# aria-BOB.net
KiCad netlist of a schematic drawn in EAGLE
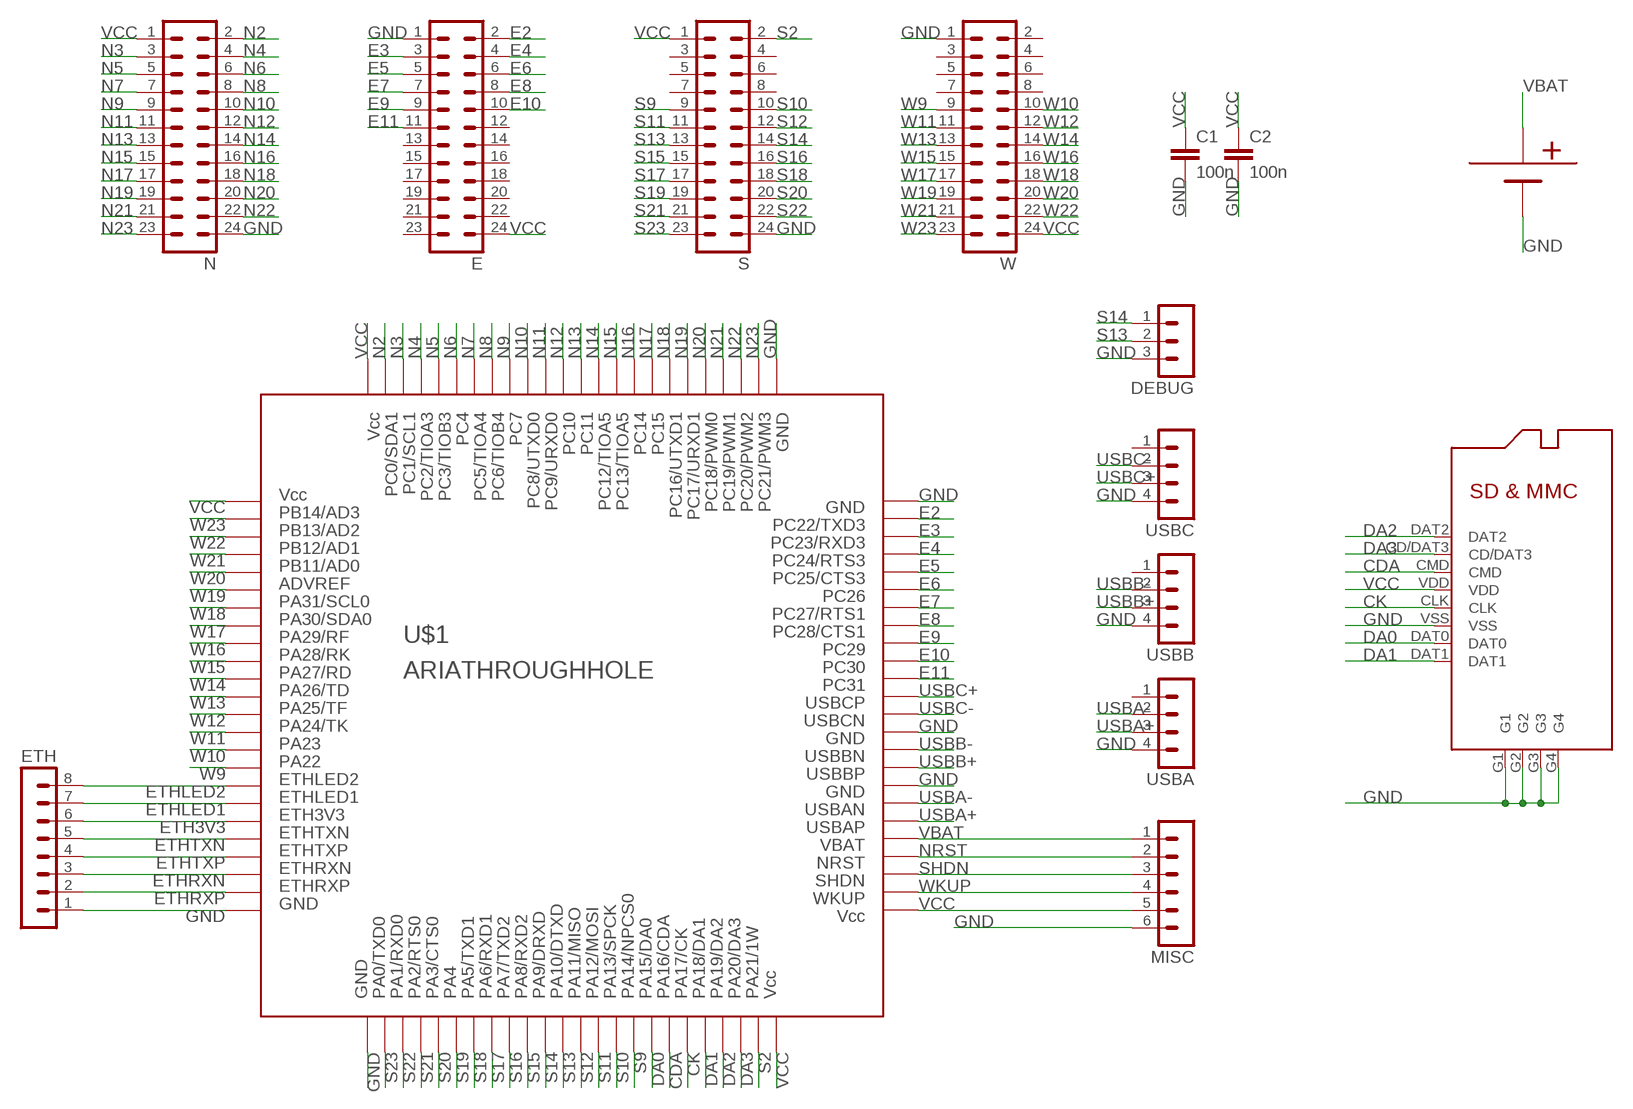
[diagram p0: schematic, sheet 1]

(export (version "E")
  (design (tool "Eeschema 10.0.6"))
  (components
    (comp (ref "C1")
      (value "100n")
      (footprint "eagle-import:C0603")
      (libsource (lib "eagle-import") (part "C-EUC0603"))
    )
    (comp (ref "C2")
      (value "100n")
      (footprint "eagle-import:C0603")
      (libsource (lib "eagle-import") (part "C-EUC0603"))
    )
    (comp (ref "DEBUG")
      (value "MA03-1")
      (footprint "eagle-import:MA03-1")
      (libsource (lib "eagle-import") (part "MA03-1"))
    )
    (comp (ref "E")
      (value "MA12-2")
      (footprint "eagle-import:MA12-2")
      (libsource (lib "eagle-import") (part "MA12-2"))
    )
    (comp (ref "ETH")
      (value "MA08-1")
      (footprint "eagle-import:MA08-1")
      (libsource (lib "eagle-import") (part "MA08-1"))
    )
    (comp (ref "MISC")
      (value "MA06-1")
      (footprint "eagle-import:MA06-1")
      (libsource (lib "eagle-import") (part "MA06-1"))
    )
    (comp (ref "N")
      (value "MA12-2")
      (footprint "eagle-import:MA12-2")
      (libsource (lib "eagle-import") (part "MA12-2"))
    )
    (comp (ref "S")
      (value "MA12-2")
      (footprint "eagle-import:MA12-2")
      (libsource (lib "eagle-import") (part "MA12-2"))
    )
    (comp (ref "U$1")
      (value "ARIATHROUGHHOLE")
      (footprint "eagle-import:ARIA-TROUGHHOLE")
      (libsource (lib "eagle-import") (part "ARIATHROUGHHOLE"))
    )
    (comp (ref "U$3")
      (value "BAT")
      (footprint "eagle-import:BAT-CR1220")
      (libsource (lib "eagle-import") (part "BAT"))
    )
    (comp (ref "U$4")
      (value "MICRO-SD")
      (footprint "eagle-import:MISCRO-SD")
      (libsource (lib "eagle-import") (part "MICRO-SD"))
    )
    (comp (ref "USBA")
      (value "MA04-1")
      (footprint "eagle-import:MA04-1")
      (libsource (lib "eagle-import") (part "MA04-1"))
    )
    (comp (ref "USBB")
      (value "MA04-1")
      (footprint "eagle-import:MA04-1")
      (libsource (lib "eagle-import") (part "MA04-1"))
    )
    (comp (ref "USBC")
      (value "MA04-1")
      (footprint "eagle-import:MA04-1")
      (libsource (lib "eagle-import") (part "MA04-1"))
    )
    (comp (ref "W")
      (value "MA12-2")
      (footprint "eagle-import:MA12-2")
      (libsource (lib "eagle-import") (part "MA12-2"))
    )
  )
  (nets
    (net (code "1") (name "/CDA") (class "Default")
      (node (ref "U$1") (pin "S7") (pinfunction "S7_S7") (pintype "bidirectional"))
      (node (ref "U$4") (pin "CMD") (pinfunction "CMD_CMD") (pintype "input"))
    )
    (net (code "2") (name "/CK") (class "Default")
      (node (ref "U$1") (pin "S6") (pinfunction "S6_S6") (pintype "bidirectional"))
      (node (ref "U$4") (pin "CLK") (pinfunction "CLK_CLK") (pintype "input"))
    )
    (net (code "3") (name "/DA0") (class "Default")
      (node (ref "U$1") (pin "S8") (pinfunction "S8_S8") (pintype "bidirectional"))
      (node (ref "U$4") (pin "DAT0") (pinfunction "DAT0_DAT0") (pintype "input"))
    )
    (net (code "4") (name "/DA1") (class "Default")
      (node (ref "U$1") (pin "S5") (pinfunction "S5_S5") (pintype "bidirectional"))
      (node (ref "U$4") (pin "DAT1") (pinfunction "DAT1_DAT1") (pintype "output"))
    )
    (net (code "5") (name "/DA2") (class "Default")
      (node (ref "U$1") (pin "S4") (pinfunction "S4_S4") (pintype "bidirectional"))
      (node (ref "U$4") (pin "DAT2") (pinfunction "DAT2_DAT2") (pintype "bidirectional"))
    )
    (net (code "6") (name "/DA3") (class "Default")
      (node (ref "U$1") (pin "S3") (pinfunction "S3_S3") (pintype "bidirectional"))
      (node (ref "U$4") (pin "CD/DAT3") (pinfunction "CD/DAT3_CD/DAT3") (pintype "bidirectional"))
    )
    (net (code "7") (name "/E2") (class "Default")
      (node (ref "E") (pin "2") (pinfunction "2_2") (pintype "passive"))
      (node (ref "U$1") (pin "E2") (pinfunction "E2_E2") (pintype "bidirectional"))
    )
    (net (code "8") (name "/E3") (class "Default")
      (node (ref "E") (pin "3") (pinfunction "3_3") (pintype "passive"))
      (node (ref "U$1") (pin "E3") (pinfunction "E3_E3") (pintype "bidirectional"))
    )
    (net (code "9") (name "/E4") (class "Default")
      (node (ref "E") (pin "4") (pinfunction "4_4") (pintype "passive"))
      (node (ref "U$1") (pin "E4") (pinfunction "E4_E4") (pintype "bidirectional"))
    )
    (net (code "10") (name "/E5") (class "Default")
      (node (ref "E") (pin "5") (pinfunction "5_5") (pintype "passive"))
      (node (ref "U$1") (pin "E5") (pinfunction "E5_E5") (pintype "bidirectional"))
    )
    (net (code "11") (name "/E6") (class "Default")
      (node (ref "E") (pin "6") (pinfunction "6_6") (pintype "passive"))
      (node (ref "U$1") (pin "E6") (pinfunction "E6_E6") (pintype "bidirectional"))
    )
    (net (code "12") (name "/E7") (class "Default")
      (node (ref "E") (pin "7") (pinfunction "7_7") (pintype "passive"))
      (node (ref "U$1") (pin "E7") (pinfunction "E7_E7") (pintype "bidirectional"))
    )
    (net (code "13") (name "/E8") (class "Default")
      (node (ref "E") (pin "8") (pinfunction "8_8") (pintype "passive"))
      (node (ref "U$1") (pin "E8") (pinfunction "E8_E8") (pintype "bidirectional"))
    )
    (net (code "14") (name "/E9") (class "Default")
      (node (ref "E") (pin "9") (pinfunction "9_9") (pintype "passive"))
      (node (ref "U$1") (pin "E9") (pinfunction "E9_E9") (pintype "bidirectional"))
    )
    (net (code "15") (name "/E10") (class "Default")
      (node (ref "E") (pin "10") (pinfunction "10_10") (pintype "passive"))
      (node (ref "U$1") (pin "E10") (pinfunction "E10_E10") (pintype "bidirectional"))
    )
    (net (code "16") (name "/E11") (class "Default")
      (node (ref "E") (pin "11") (pinfunction "11_11") (pintype "passive"))
      (node (ref "U$1") (pin "E11") (pinfunction "E11_E11") (pintype "bidirectional"))
    )
    (net (code "17") (name "/ETH3V3") (class "Default")
      (node (ref "ETH") (pin "6") (pinfunction "6_6") (pintype "passive"))
      (node (ref "U$1") (pin "W6") (pinfunction "W6_W6") (pintype "bidirectional"))
    )
    (net (code "18") (name "/ETHLED1") (class "Default")
      (node (ref "ETH") (pin "7") (pinfunction "7_7") (pintype "passive"))
      (node (ref "U$1") (pin "W7") (pinfunction "W7_W7") (pintype "bidirectional"))
    )
    (net (code "19") (name "/ETHLED2") (class "Default")
      (node (ref "ETH") (pin "8") (pinfunction "8_8") (pintype "passive"))
      (node (ref "U$1") (pin "W8") (pinfunction "W8_W8") (pintype "bidirectional"))
    )
    (net (code "20") (name "/ETHRXN") (class "Default")
      (node (ref "ETH") (pin "3") (pinfunction "3_3") (pintype "passive"))
      (node (ref "U$1") (pin "W3") (pinfunction "W3_W3") (pintype "bidirectional"))
    )
    (net (code "21") (name "/ETHRXP") (class "Default")
      (node (ref "ETH") (pin "2") (pinfunction "2_2") (pintype "passive"))
      (node (ref "U$1") (pin "W2") (pinfunction "W2_W2") (pintype "bidirectional"))
    )
    (net (code "22") (name "/ETHTXN") (class "Default")
      (node (ref "ETH") (pin "5") (pinfunction "5_5") (pintype "passive"))
      (node (ref "U$1") (pin "W5") (pinfunction "W5_W5") (pintype "bidirectional"))
    )
    (net (code "23") (name "/ETHTXP") (class "Default")
      (node (ref "ETH") (pin "4") (pinfunction "4_4") (pintype "passive"))
      (node (ref "U$1") (pin "W4") (pinfunction "W4_W4") (pintype "bidirectional"))
    )
    (net (code "24") (name "/GND") (class "Default")
      (node (ref "C1") (pin "2") (pinfunction "2_2") (pintype "passive"))
      (node (ref "C2") (pin "2") (pinfunction "2_2") (pintype "passive"))
      (node (ref "DEBUG") (pin "3") (pinfunction "3_3") (pintype "passive"))
      (node (ref "E") (pin "1") (pinfunction "1_1") (pintype "passive"))
      (node (ref "ETH") (pin "1") (pinfunction "1_1") (pintype "passive"))
      (node (ref "MISC") (pin "6") (pinfunction "6_6") (pintype "passive"))
      (node (ref "N") (pin "24") (pinfunction "24_24") (pintype "passive"))
      (node (ref "S") (pin "24") (pinfunction "24_24") (pintype "passive"))
      (node (ref "U$1") (pin "E1") (pinfunction "E1_E1") (pintype "bidirectional"))
      (node (ref "U$1") (pin "E14") (pinfunction "E14_E14") (pintype "bidirectional"))
      (node (ref "U$1") (pin "E17") (pinfunction "E17_E17") (pintype "bidirectional"))
      (node (ref "U$1") (pin "N24") (pinfunction "N24_N24") (pintype "bidirectional"))
      (node (ref "U$1") (pin "S24") (pinfunction "S24_S24") (pintype "bidirectional"))
      (node (ref "U$1") (pin "W1") (pinfunction "W1_W1") (pintype "bidirectional"))
      (node (ref "U$3") (pin "BAT-") (pinfunction "BAT-_BAT-") (pintype "bidirectional"))
      (node (ref "U$4") (pin "G1") (pinfunction "G1_G1") (pintype "bidirectional"))
      (node (ref "U$4") (pin "G2") (pinfunction "G2_G2") (pintype "bidirectional"))
      (node (ref "U$4") (pin "G3") (pinfunction "G3_G3") (pintype "bidirectional"))
      (node (ref "U$4") (pin "G4") (pinfunction "G4_G4") (pintype "bidirectional"))
      (node (ref "U$4") (pin "VSS") (pinfunction "VSS_VSS") (pintype "power_in"))
      (node (ref "USBA") (pin "4") (pinfunction "4_4") (pintype "passive"))
      (node (ref "USBB") (pin "4") (pinfunction "4_4") (pintype "passive"))
      (node (ref "USBC") (pin "4") (pinfunction "4_4") (pintype "passive"))
      (node (ref "W") (pin "1") (pinfunction "1_1") (pintype "passive"))
    )
    (net (code "25") (name "/N2") (class "Default")
      (node (ref "N") (pin "2") (pinfunction "2_2") (pintype "passive"))
      (node (ref "U$1") (pin "N2") (pinfunction "N2_N2") (pintype "bidirectional"))
    )
    (net (code "26") (name "/N3") (class "Default")
      (node (ref "N") (pin "3") (pinfunction "3_3") (pintype "passive"))
      (node (ref "U$1") (pin "N3") (pinfunction "N3_N3") (pintype "bidirectional"))
    )
    (net (code "27") (name "/N4") (class "Default")
      (node (ref "N") (pin "4") (pinfunction "4_4") (pintype "passive"))
      (node (ref "U$1") (pin "N4") (pinfunction "N4_N4") (pintype "bidirectional"))
    )
    (net (code "28") (name "/N5") (class "Default")
      (node (ref "N") (pin "5") (pinfunction "5_5") (pintype "passive"))
      (node (ref "U$1") (pin "N5") (pinfunction "N5_N5") (pintype "bidirectional"))
    )
    (net (code "29") (name "/N6") (class "Default")
      (node (ref "N") (pin "6") (pinfunction "6_6") (pintype "passive"))
      (node (ref "U$1") (pin "N6") (pinfunction "N6_N6") (pintype "bidirectional"))
    )
    (net (code "30") (name "/N7") (class "Default")
      (node (ref "N") (pin "7") (pinfunction "7_7") (pintype "passive"))
      (node (ref "U$1") (pin "N7") (pinfunction "N7_N7") (pintype "bidirectional"))
    )
    (net (code "31") (name "/N8") (class "Default")
      (node (ref "N") (pin "8") (pinfunction "8_8") (pintype "passive"))
      (node (ref "U$1") (pin "N8") (pinfunction "N8_N8") (pintype "bidirectional"))
    )
    (net (code "32") (name "/N9") (class "Default")
      (node (ref "N") (pin "9") (pinfunction "9_9") (pintype "passive"))
      (node (ref "U$1") (pin "N9") (pinfunction "N9_N9") (pintype "bidirectional"))
    )
    (net (code "33") (name "/N10") (class "Default")
      (node (ref "N") (pin "10") (pinfunction "10_10") (pintype "passive"))
      (node (ref "U$1") (pin "N10") (pinfunction "N10_N10") (pintype "bidirectional"))
    )
    (net (code "34") (name "/N11") (class "Default")
      (node (ref "N") (pin "11") (pinfunction "11_11") (pintype "passive"))
      (node (ref "U$1") (pin "N11") (pinfunction "N11_N11") (pintype "bidirectional"))
    )
    (net (code "35") (name "/N12") (class "Default")
      (node (ref "N") (pin "12") (pinfunction "12_12") (pintype "passive"))
      (node (ref "U$1") (pin "N12") (pinfunction "N12_N12") (pintype "bidirectional"))
    )
    (net (code "36") (name "/N13") (class "Default")
      (node (ref "N") (pin "13") (pinfunction "13_13") (pintype "passive"))
      (node (ref "U$1") (pin "N13") (pinfunction "N13_N13") (pintype "bidirectional"))
    )
    (net (code "37") (name "/N14") (class "Default")
      (node (ref "N") (pin "14") (pinfunction "14_14") (pintype "passive"))
      (node (ref "U$1") (pin "N14") (pinfunction "N14_N14") (pintype "bidirectional"))
    )
    (net (code "38") (name "/N15") (class "Default")
      (node (ref "N") (pin "15") (pinfunction "15_15") (pintype "passive"))
      (node (ref "U$1") (pin "N15") (pinfunction "N15_N15") (pintype "bidirectional"))
    )
    (net (code "39") (name "/N16") (class "Default")
      (node (ref "N") (pin "16") (pinfunction "16_16") (pintype "passive"))
      (node (ref "U$1") (pin "N16") (pinfunction "N16_N16") (pintype "bidirectional"))
    )
    (net (code "40") (name "/N17") (class "Default")
      (node (ref "N") (pin "17") (pinfunction "17_17") (pintype "passive"))
      (node (ref "U$1") (pin "N17") (pinfunction "N17_N17") (pintype "bidirectional"))
    )
    (net (code "41") (name "/N18") (class "Default")
      (node (ref "N") (pin "18") (pinfunction "18_18") (pintype "passive"))
      (node (ref "U$1") (pin "N18") (pinfunction "N18_N18") (pintype "bidirectional"))
    )
    (net (code "42") (name "/N19") (class "Default")
      (node (ref "N") (pin "19") (pinfunction "19_19") (pintype "passive"))
      (node (ref "U$1") (pin "N19") (pinfunction "N19_N19") (pintype "bidirectional"))
    )
    (net (code "43") (name "/N20") (class "Default")
      (node (ref "N") (pin "20") (pinfunction "20_20") (pintype "passive"))
      (node (ref "U$1") (pin "N20") (pinfunction "N20_N20") (pintype "bidirectional"))
    )
    (net (code "44") (name "/N21") (class "Default")
      (node (ref "N") (pin "21") (pinfunction "21_21") (pintype "passive"))
      (node (ref "U$1") (pin "N21") (pinfunction "N21_N21") (pintype "bidirectional"))
    )
    (net (code "45") (name "/N22") (class "Default")
      (node (ref "N") (pin "22") (pinfunction "22_22") (pintype "passive"))
      (node (ref "U$1") (pin "N22") (pinfunction "N22_N22") (pintype "bidirectional"))
    )
    (net (code "46") (name "/N23") (class "Default")
      (node (ref "N") (pin "23") (pinfunction "23_23") (pintype "passive"))
      (node (ref "U$1") (pin "N23") (pinfunction "N23_N23") (pintype "bidirectional"))
    )
    (net (code "47") (name "/NRST") (class "Default")
      (node (ref "MISC") (pin "2") (pinfunction "2_2") (pintype "passive"))
      (node (ref "U$1") (pin "E21") (pinfunction "E21_E21") (pintype "bidirectional"))
    )
    (net (code "48") (name "/S2") (class "Default")
      (node (ref "S") (pin "2") (pinfunction "2_2") (pintype "passive"))
      (node (ref "U$1") (pin "S2") (pinfunction "S2_S2") (pintype "bidirectional"))
    )
    (net (code "49") (name "/S9") (class "Default")
      (node (ref "S") (pin "9") (pinfunction "9_9") (pintype "passive"))
      (node (ref "U$1") (pin "S9") (pinfunction "S9_S9") (pintype "bidirectional"))
    )
    (net (code "50") (name "/S10") (class "Default")
      (node (ref "S") (pin "10") (pinfunction "10_10") (pintype "passive"))
      (node (ref "U$1") (pin "S10") (pinfunction "S10_S10") (pintype "bidirectional"))
    )
    (net (code "51") (name "/S11") (class "Default")
      (node (ref "S") (pin "11") (pinfunction "11_11") (pintype "passive"))
      (node (ref "U$1") (pin "S11") (pinfunction "S11_S11") (pintype "bidirectional"))
    )
    (net (code "52") (name "/S12") (class "Default")
      (node (ref "S") (pin "12") (pinfunction "12_12") (pintype "passive"))
      (node (ref "U$1") (pin "S12") (pinfunction "S12_S12") (pintype "bidirectional"))
    )
    (net (code "53") (name "/S13") (class "Default")
      (node (ref "DEBUG") (pin "2") (pinfunction "2_2") (pintype "passive"))
      (node (ref "S") (pin "13") (pinfunction "13_13") (pintype "passive"))
      (node (ref "U$1") (pin "S13") (pinfunction "S13_S13") (pintype "bidirectional"))
    )
    (net (code "54") (name "/S14") (class "Default")
      (node (ref "DEBUG") (pin "1") (pinfunction "1_1") (pintype "passive"))
      (node (ref "S") (pin "14") (pinfunction "14_14") (pintype "passive"))
      (node (ref "U$1") (pin "S14") (pinfunction "S14_S14") (pintype "bidirectional"))
    )
    (net (code "55") (name "/S15") (class "Default")
      (node (ref "S") (pin "15") (pinfunction "15_15") (pintype "passive"))
      (node (ref "U$1") (pin "S15") (pinfunction "S15_S15") (pintype "bidirectional"))
    )
    (net (code "56") (name "/S16") (class "Default")
      (node (ref "S") (pin "16") (pinfunction "16_16") (pintype "passive"))
      (node (ref "U$1") (pin "S16") (pinfunction "S16_S16") (pintype "bidirectional"))
    )
    (net (code "57") (name "/S17") (class "Default")
      (node (ref "S") (pin "17") (pinfunction "17_17") (pintype "passive"))
      (node (ref "U$1") (pin "S17") (pinfunction "S17_S17") (pintype "bidirectional"))
    )
    (net (code "58") (name "/S18") (class "Default")
      (node (ref "S") (pin "18") (pinfunction "18_18") (pintype "passive"))
      (node (ref "U$1") (pin "S18") (pinfunction "S18_S18") (pintype "bidirectional"))
    )
    (net (code "59") (name "/S19") (class "Default")
      (node (ref "S") (pin "19") (pinfunction "19_19") (pintype "passive"))
      (node (ref "U$1") (pin "S19") (pinfunction "S19_S19") (pintype "bidirectional"))
    )
    (net (code "60") (name "/S20") (class "Default")
      (node (ref "S") (pin "20") (pinfunction "20_20") (pintype "passive"))
      (node (ref "U$1") (pin "S20") (pinfunction "S20_S20") (pintype "bidirectional"))
    )
    (net (code "61") (name "/S21") (class "Default")
      (node (ref "S") (pin "21") (pinfunction "21_21") (pintype "passive"))
      (node (ref "U$1") (pin "S21") (pinfunction "S21_S21") (pintype "bidirectional"))
    )
    (net (code "62") (name "/S22") (class "Default")
      (node (ref "S") (pin "22") (pinfunction "22_22") (pintype "passive"))
      (node (ref "U$1") (pin "S22") (pinfunction "S22_S22") (pintype "bidirectional"))
    )
    (net (code "63") (name "/S23") (class "Default")
      (node (ref "S") (pin "23") (pinfunction "23_23") (pintype "passive"))
      (node (ref "U$1") (pin "S23") (pinfunction "S23_S23") (pintype "bidirectional"))
    )
    (net (code "64") (name "/SHDN") (class "Default")
      (node (ref "MISC") (pin "3") (pinfunction "3_3") (pintype "passive"))
      (node (ref "U$1") (pin "E22") (pinfunction "E22_E22") (pintype "bidirectional"))
    )
    (net (code "65") (name "/USBA+") (class "Default")
      (node (ref "U$1") (pin "E19") (pinfunction "E19_E19") (pintype "bidirectional"))
      (node (ref "USBA") (pin "3") (pinfunction "3_3") (pintype "passive"))
    )
    (net (code "66") (name "/USBA-") (class "Default")
      (node (ref "U$1") (pin "E18") (pinfunction "E18_E18") (pintype "bidirectional"))
      (node (ref "USBA") (pin "2") (pinfunction "2_2") (pintype "passive"))
    )
    (net (code "67") (name "/USBB+") (class "Default")
      (node (ref "U$1") (pin "E16") (pinfunction "E16_E16") (pintype "bidirectional"))
      (node (ref "USBB") (pin "3") (pinfunction "3_3") (pintype "passive"))
    )
    (net (code "68") (name "/USBB-") (class "Default")
      (node (ref "U$1") (pin "E15") (pinfunction "E15_E15") (pintype "bidirectional"))
      (node (ref "USBB") (pin "2") (pinfunction "2_2") (pintype "passive"))
    )
    (net (code "69") (name "/USBC+") (class "Default")
      (node (ref "U$1") (pin "E12") (pinfunction "E12_E12") (pintype "bidirectional"))
      (node (ref "USBC") (pin "3") (pinfunction "3_3") (pintype "passive"))
    )
    (net (code "70") (name "/USBC-") (class "Default")
      (node (ref "U$1") (pin "E13") (pinfunction "E13_E13") (pintype "bidirectional"))
      (node (ref "USBC") (pin "2") (pinfunction "2_2") (pintype "passive"))
    )
    (net (code "71") (name "/VBAT") (class "Default")
      (node (ref "MISC") (pin "1") (pinfunction "1_1") (pintype "passive"))
      (node (ref "U$1") (pin "E20") (pinfunction "E20_E20") (pintype "bidirectional"))
      (node (ref "U$3") (pin "BAT+") (pinfunction "BAT+_BAT+") (pintype "bidirectional"))
      (node (ref "U$3") (pin "BAT1+") (pinfunction "BAT+_BAT1+") (pintype "bidirectional"))
    )
    (net (code "72") (name "/VCC") (class "Default")
      (node (ref "C1") (pin "1") (pinfunction "1_1") (pintype "passive"))
      (node (ref "C2") (pin "1") (pinfunction "1_1") (pintype "passive"))
      (node (ref "E") (pin "24") (pinfunction "24_24") (pintype "passive"))
      (node (ref "MISC") (pin "5") (pinfunction "5_5") (pintype "passive"))
      (node (ref "N") (pin "1") (pinfunction "1_1") (pintype "passive"))
      (node (ref "S") (pin "1") (pinfunction "1_1") (pintype "passive"))
      (node (ref "U$1") (pin "E24") (pinfunction "E24_E24") (pintype "bidirectional"))
      (node (ref "U$1") (pin "N1") (pinfunction "N1_N1") (pintype "bidirectional"))
      (node (ref "U$1") (pin "S1") (pinfunction "S1_S1") (pintype "bidirectional"))
      (node (ref "U$1") (pin "W24") (pinfunction "W24_W24") (pintype "bidirectional"))
      (node (ref "U$4") (pin "VDD") (pinfunction "VDD_VDD") (pintype "power_in"))
      (node (ref "W") (pin "24") (pinfunction "24_24") (pintype "passive"))
    )
    (net (code "73") (name "/W9") (class "Default")
      (node (ref "U$1") (pin "W9") (pinfunction "W9_W9") (pintype "bidirectional"))
      (node (ref "W") (pin "9") (pinfunction "9_9") (pintype "passive"))
    )
    (net (code "74") (name "/W10") (class "Default")
      (node (ref "U$1") (pin "W10") (pinfunction "W10_W10") (pintype "bidirectional"))
      (node (ref "W") (pin "10") (pinfunction "10_10") (pintype "passive"))
    )
    (net (code "75") (name "/W11") (class "Default")
      (node (ref "U$1") (pin "W11") (pinfunction "W11_W11") (pintype "bidirectional"))
      (node (ref "W") (pin "11") (pinfunction "11_11") (pintype "passive"))
    )
    (net (code "76") (name "/W12") (class "Default")
      (node (ref "U$1") (pin "W12") (pinfunction "W12_W12") (pintype "bidirectional"))
      (node (ref "W") (pin "12") (pinfunction "12_12") (pintype "passive"))
    )
    (net (code "77") (name "/W13") (class "Default")
      (node (ref "U$1") (pin "W13") (pinfunction "W13_W13") (pintype "bidirectional"))
      (node (ref "W") (pin "13") (pinfunction "13_13") (pintype "passive"))
    )
    (net (code "78") (name "/W14") (class "Default")
      (node (ref "U$1") (pin "W14") (pinfunction "W14_W14") (pintype "bidirectional"))
      (node (ref "W") (pin "14") (pinfunction "14_14") (pintype "passive"))
    )
    (net (code "79") (name "/W15") (class "Default")
      (node (ref "U$1") (pin "W15") (pinfunction "W15_W15") (pintype "bidirectional"))
      (node (ref "W") (pin "15") (pinfunction "15_15") (pintype "passive"))
    )
    (net (code "80") (name "/W16") (class "Default")
      (node (ref "U$1") (pin "W16") (pinfunction "W16_W16") (pintype "bidirectional"))
      (node (ref "W") (pin "16") (pinfunction "16_16") (pintype "passive"))
    )
    (net (code "81") (name "/W17") (class "Default")
      (node (ref "U$1") (pin "W17") (pinfunction "W17_W17") (pintype "bidirectional"))
      (node (ref "W") (pin "17") (pinfunction "17_17") (pintype "passive"))
    )
    (net (code "82") (name "/W18") (class "Default")
      (node (ref "U$1") (pin "W18") (pinfunction "W18_W18") (pintype "bidirectional"))
      (node (ref "W") (pin "18") (pinfunction "18_18") (pintype "passive"))
    )
    (net (code "83") (name "/W19") (class "Default")
      (node (ref "U$1") (pin "W19") (pinfunction "W19_W19") (pintype "bidirectional"))
      (node (ref "W") (pin "19") (pinfunction "19_19") (pintype "passive"))
    )
    (net (code "84") (name "/W20") (class "Default")
      (node (ref "U$1") (pin "W20") (pinfunction "W20_W20") (pintype "bidirectional"))
      (node (ref "W") (pin "20") (pinfunction "20_20") (pintype "passive"))
    )
    (net (code "85") (name "/W21") (class "Default")
      (node (ref "U$1") (pin "W21") (pinfunction "W21_W21") (pintype "bidirectional"))
      (node (ref "W") (pin "21") (pinfunction "21_21") (pintype "passive"))
    )
    (net (code "86") (name "/W22") (class "Default")
      (node (ref "U$1") (pin "W22") (pinfunction "W22_W22") (pintype "bidirectional"))
      (node (ref "W") (pin "22") (pinfunction "22_22") (pintype "passive"))
    )
    (net (code "87") (name "/W23") (class "Default")
      (node (ref "U$1") (pin "W23") (pinfunction "W23_W23") (pintype "bidirectional"))
      (node (ref "W") (pin "23") (pinfunction "23_23") (pintype "passive"))
    )
    (net (code "88") (name "/WKUP") (class "Default")
      (node (ref "MISC") (pin "4") (pinfunction "4_4") (pintype "passive"))
      (node (ref "U$1") (pin "E23") (pinfunction "E23_E23") (pintype "bidirectional"))
    )
    (net (code "89") (name "unconnected-(E-Pad12)") (class "Default")
      (node (ref "E") (pin "12") (pinfunction "12_12") (pintype "passive"))
    )
    (net (code "90") (name "unconnected-(E-Pad13)") (class "Default")
      (node (ref "E") (pin "13") (pinfunction "13_13") (pintype "passive"))
    )
    (net (code "91") (name "unconnected-(E-Pad14)") (class "Default")
      (node (ref "E") (pin "14") (pinfunction "14_14") (pintype "passive"))
    )
    (net (code "92") (name "unconnected-(E-Pad15)") (class "Default")
      (node (ref "E") (pin "15") (pinfunction "15_15") (pintype "passive"))
    )
    (net (code "93") (name "unconnected-(E-Pad16)") (class "Default")
      (node (ref "E") (pin "16") (pinfunction "16_16") (pintype "passive"))
    )
    (net (code "94") (name "unconnected-(E-Pad17)") (class "Default")
      (node (ref "E") (pin "17") (pinfunction "17_17") (pintype "passive"))
    )
    (net (code "95") (name "unconnected-(E-Pad18)") (class "Default")
      (node (ref "E") (pin "18") (pinfunction "18_18") (pintype "passive"))
    )
    (net (code "96") (name "unconnected-(E-Pad19)") (class "Default")
      (node (ref "E") (pin "19") (pinfunction "19_19") (pintype "passive"))
    )
    (net (code "97") (name "unconnected-(E-Pad20)") (class "Default")
      (node (ref "E") (pin "20") (pinfunction "20_20") (pintype "passive"))
    )
    (net (code "98") (name "unconnected-(E-Pad21)") (class "Default")
      (node (ref "E") (pin "21") (pinfunction "21_21") (pintype "passive"))
    )
    (net (code "99") (name "unconnected-(E-Pad22)") (class "Default")
      (node (ref "E") (pin "22") (pinfunction "22_22") (pintype "passive"))
    )
    (net (code "100") (name "unconnected-(E-Pad23)") (class "Default")
      (node (ref "E") (pin "23") (pinfunction "23_23") (pintype "passive"))
    )
    (net (code "101") (name "unconnected-(S-Pad3)") (class "Default")
      (node (ref "S") (pin "3") (pinfunction "3_3") (pintype "passive"))
    )
    (net (code "102") (name "unconnected-(S-Pad4)") (class "Default")
      (node (ref "S") (pin "4") (pinfunction "4_4") (pintype "passive"))
    )
    (net (code "103") (name "unconnected-(S-Pad5)") (class "Default")
      (node (ref "S") (pin "5") (pinfunction "5_5") (pintype "passive"))
    )
    (net (code "104") (name "unconnected-(S-Pad6)") (class "Default")
      (node (ref "S") (pin "6") (pinfunction "6_6") (pintype "passive"))
    )
    (net (code "105") (name "unconnected-(S-Pad7)") (class "Default")
      (node (ref "S") (pin "7") (pinfunction "7_7") (pintype "passive"))
    )
    (net (code "106") (name "unconnected-(S-Pad8)") (class "Default")
      (node (ref "S") (pin "8") (pinfunction "8_8") (pintype "passive"))
    )
    (net (code "107") (name "unconnected-(USBA-Pad1)") (class "Default")
      (node (ref "USBA") (pin "1") (pinfunction "1_1") (pintype "passive"))
    )
    (net (code "108") (name "unconnected-(USBB-Pad1)") (class "Default")
      (node (ref "USBB") (pin "1") (pinfunction "1_1") (pintype "passive"))
    )
    (net (code "109") (name "unconnected-(USBC-Pad1)") (class "Default")
      (node (ref "USBC") (pin "1") (pinfunction "1_1") (pintype "passive"))
    )
    (net (code "110") (name "unconnected-(W-Pad2)") (class "Default")
      (node (ref "W") (pin "2") (pinfunction "2_2") (pintype "passive"))
    )
    (net (code "111") (name "unconnected-(W-Pad3)") (class "Default")
      (node (ref "W") (pin "3") (pinfunction "3_3") (pintype "passive"))
    )
    (net (code "112") (name "unconnected-(W-Pad4)") (class "Default")
      (node (ref "W") (pin "4") (pinfunction "4_4") (pintype "passive"))
    )
    (net (code "113") (name "unconnected-(W-Pad5)") (class "Default")
      (node (ref "W") (pin "5") (pinfunction "5_5") (pintype "passive"))
    )
    (net (code "114") (name "unconnected-(W-Pad6)") (class "Default")
      (node (ref "W") (pin "6") (pinfunction "6_6") (pintype "passive"))
    )
    (net (code "115") (name "unconnected-(W-Pad7)") (class "Default")
      (node (ref "W") (pin "7") (pinfunction "7_7") (pintype "passive"))
    )
    (net (code "116") (name "unconnected-(W-Pad8)") (class "Default")
      (node (ref "W") (pin "8") (pinfunction "8_8") (pintype "passive"))
    )
  )
)
